# peripherals.net
KiCad netlist of a schematic drawn in Altium Designer
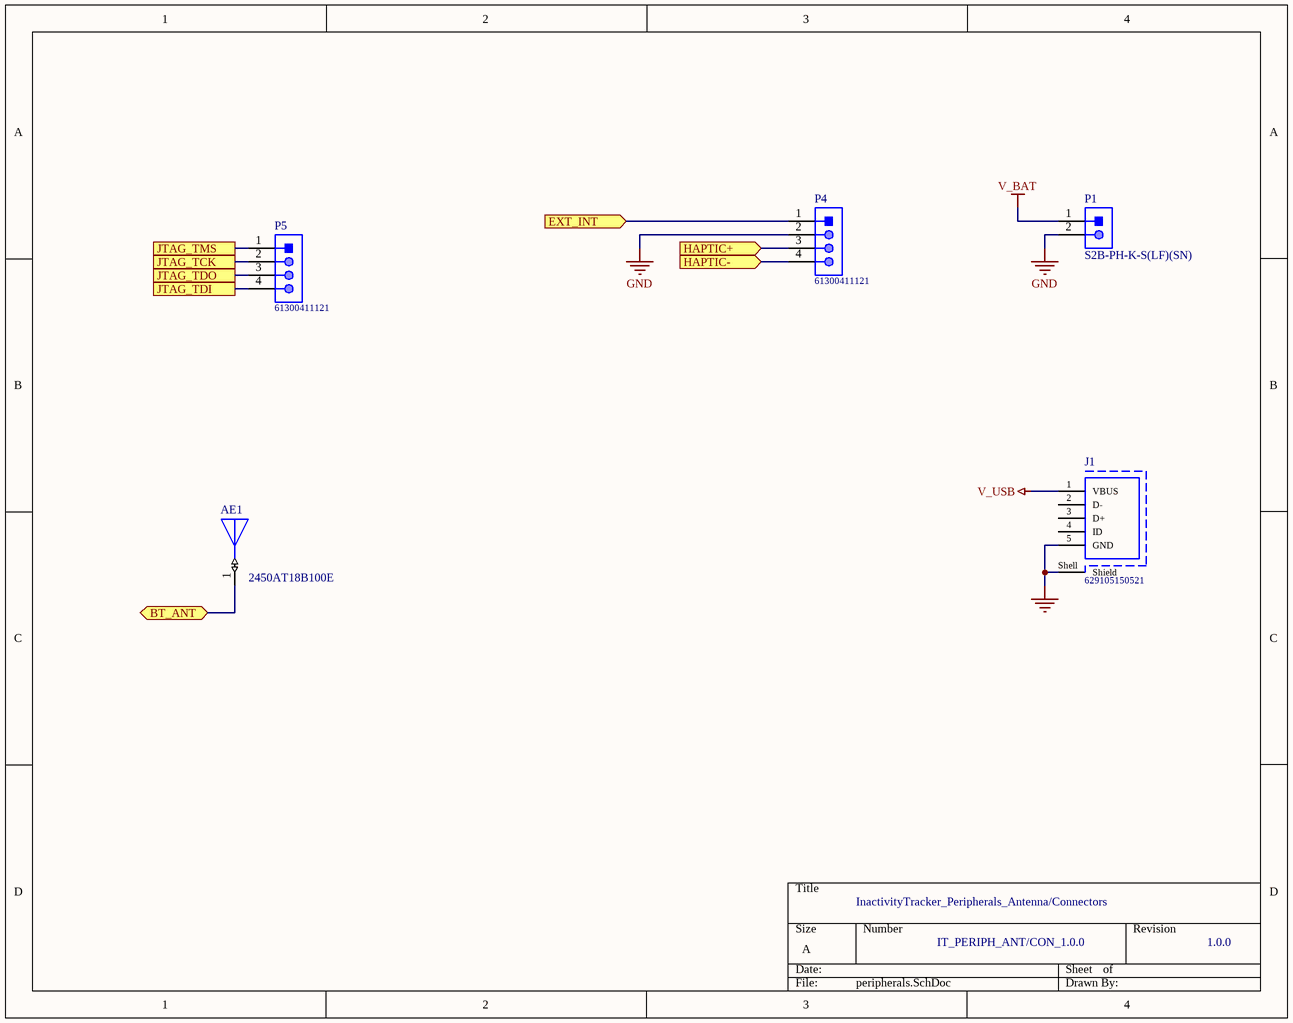
[diagram p0: peripherals.SchDoc]

(export (version "E")
  (design (tool "Eeschema 10.0.6"))
  (components
    (comp (ref "AE1")
      (value "2450AT18B100E")
      (footprint "ANT_2450AT18B100E")
      (description "JOHANSON TECHNOLOGY - 2450AT18B100E - ANTENNA, CERAMIC, 2.45GHZ")
      (fields (field (name "MANUFACTURER") "Johanson"))
      (libsource (lib "InactivityTracker") (part "2450AT18B100E"))
    )
    (comp (ref "J1")
      (value "629105150521")
      (footprint "629105150521")
      (description "Micro USB 2.0 Type B Receptacle WR-COM, Horizontal, SMT, with Pegs, High Current at Pin 1 & Pin 5")
      (fields (field (name "MANUFACTURER") "Wurth Elektronik") (field (name "PUBLISHER") "WurthElektronik"))
      (libsource (lib "Altium Content Vault") (part "WE-USB-5-1SHLD"))
    )
    (comp (ref "P1")
      (value "S2B-PH-K-S(LF)(SN)")
      (footprint "JST-S2B-PH-K-S_V")
      (fields (field (name "TOLERANCE") "20%"))
      (libsource (lib "Altium Content Vault") (part "CN-1P-M-R2"))
    )
    (comp (ref "P4")
      (value "61300411121")
      (footprint "61300411121")
      (description "THT Vertical Pin Header WR-PHD, Pitch 2.54 mm, Single Row, 4 pins")
      (fields (field (name "MANUFACTURER") "Wurth Elektronik") (field (name "PUBLISHER") "WurthElektronik"))
      (libsource (lib "Altium Content Vault") (part "WE-CN-1P-M-R4"))
    )
    (comp (ref "P5")
      (value "61300411121")
      (footprint "61300411121")
      (description "THT Vertical Pin Header WR-PHD, Pitch 2.54 mm, Single Row, 4 pins")
      (fields (field (name "MANUFACTURER") "Wurth Elektronik") (field (name "PUBLISHER") "WurthElektronik"))
      (libsource (lib "Altium Content Vault") (part "WE-CN-1P-M-R4"))
    )
  )
  (nets
    (net (code "1") (name "/BT_ANT") (class "Default")
      (node (ref "AE1") (pin "1") (pinfunction "1_1") (pintype "bidirectional"))
    )
    (net (code "2") (name "/EXT_INT") (class "Default")
      (node (ref "P4") (pin "1") (pinfunction "1_1") (pintype "passive"))
    )
    (net (code "3") (name "/HAPTIC+") (class "Default")
      (node (ref "P4") (pin "3") (pinfunction "3_3") (pintype "passive"))
    )
    (net (code "4") (name "/HAPTIC-") (class "Default")
      (node (ref "P4") (pin "4") (pinfunction "4_4") (pintype "passive"))
    )
    (net (code "5") (name "/JTAG_TCK") (class "Default")
      (node (ref "P5") (pin "2") (pinfunction "2_2") (pintype "passive"))
    )
    (net (code "6") (name "/JTAG_TDI") (class "Default")
      (node (ref "P5") (pin "4") (pinfunction "4_4") (pintype "passive"))
    )
    (net (code "7") (name "/JTAG_TDO") (class "Default")
      (node (ref "P5") (pin "3") (pinfunction "3_3") (pintype "passive"))
    )
    (net (code "8") (name "/JTAG_TMS") (class "Default")
      (node (ref "P5") (pin "1") (pinfunction "1_1") (pintype "passive"))
    )
    (net (code "9") (name "GND") (class "Default")
      (node (ref "J1") (pin "5") (pinfunction "GND_5") (pintype "passive"))
      (node (ref "J1") (pin "Shell") (pinfunction "Shield_Shell") (pintype "passive"))
      (node (ref "P1") (pin "2") (pinfunction "2_2") (pintype "passive"))
      (node (ref "P4") (pin "2") (pinfunction "2_2") (pintype "passive"))
    )
    (net (code "10") (name "V_BAT") (class "Default")
      (node (ref "P1") (pin "1") (pinfunction "1_1") (pintype "passive"))
    )
    (net (code "11") (name "V_USB") (class "Default")
      (node (ref "J1") (pin "1") (pinfunction "VBUS_1") (pintype "passive"))
    )
    (net (code "12") (name "unconnected-(J1-D+-Pad3)") (class "Default")
      (node (ref "J1") (pin "3") (pinfunction "D+_3") (pintype "passive"))
    )
    (net (code "13") (name "unconnected-(J1-D--Pad2)") (class "Default")
      (node (ref "J1") (pin "2") (pinfunction "D-_2") (pintype "passive"))
    )
    (net (code "14") (name "unconnected-(J1-ID-Pad4)") (class "Default")
      (node (ref "J1") (pin "4") (pinfunction "ID_4") (pintype "passive"))
    )
  )
)
